# schema.net
KiCad netlist of a schematic drawn in EAGLE
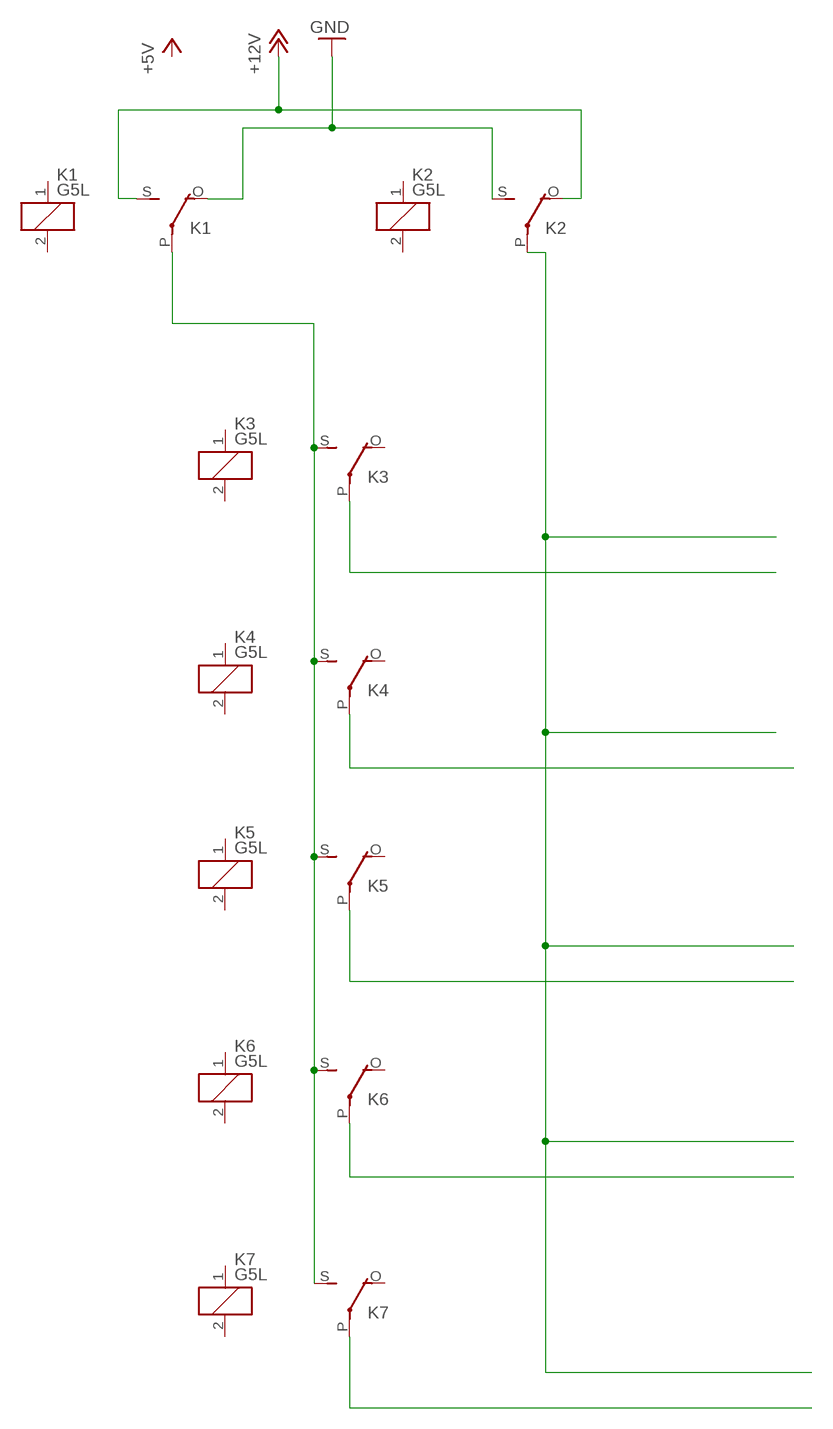
[diagram p0: schematic, sheet 1]

(export (version "E")
  (design (tool "Eeschema 10.0.6"))
  (components
    (comp (ref "K1")
      (value "G5L")
      (footprint "eagle-import:G5LE")
      (libsource (lib "eagle-import") (part "G5L"))
    )
    (comp (ref "K2")
      (value "G5L")
      (footprint "eagle-import:G5LE")
      (libsource (lib "eagle-import") (part "G5L"))
    )
    (comp (ref "K3")
      (value "G5L")
      (footprint "eagle-import:G5LE")
      (libsource (lib "eagle-import") (part "G5L"))
    )
    (comp (ref "K4")
      (value "G5L")
      (footprint "eagle-import:G5LE")
      (libsource (lib "eagle-import") (part "G5L"))
    )
    (comp (ref "K5")
      (value "G5L")
      (footprint "eagle-import:G5LE")
      (libsource (lib "eagle-import") (part "G5L"))
    )
    (comp (ref "K6")
      (value "G5L")
      (footprint "eagle-import:G5LE")
      (libsource (lib "eagle-import") (part "G5L"))
    )
    (comp (ref "K7")
      (value "G5L")
      (footprint "eagle-import:G5LE")
      (libsource (lib "eagle-import") (part "G5L"))
    )
  )
  (nets
    (net (code "2") (name "+12V") (class "Default")
      (node (ref "K1") (pin "S") (pinfunction "S_S") (pintype "passive"))
      (node (ref "K2") (pin "O") (pinfunction "O_O") (pintype "passive"))
    )
    (net (code "3") (name "GND") (class "Default")
      (node (ref "K1") (pin "O") (pinfunction "O_O") (pintype "passive"))
      (node (ref "K2") (pin "S") (pinfunction "S_S") (pintype "passive"))
    )
    (net (code "4") (name "Net-(K1-PadP)") (class "Default")
      (node (ref "K1") (pin "P") (pinfunction "P_P") (pintype "passive"))
      (node (ref "K3") (pin "S") (pinfunction "S_S") (pintype "passive"))
      (node (ref "K4") (pin "S") (pinfunction "S_S") (pintype "passive"))
      (node (ref "K5") (pin "S") (pinfunction "S_S") (pintype "passive"))
      (node (ref "K6") (pin "S") (pinfunction "S_S") (pintype "passive"))
      (node (ref "K7") (pin "S") (pinfunction "S_S") (pintype "passive"))
    )
    (net (code "5") (name "unconnected-(K1-Pad1)") (class "Default")
      (node (ref "K1") (pin "1") (pinfunction "1_1") (pintype "passive"))
    )
    (net (code "6") (name "unconnected-(K1-Pad2)") (class "Default")
      (node (ref "K1") (pin "2") (pinfunction "2_2") (pintype "passive"))
    )
    (net (code "7") (name "unconnected-(K2-Pad1)") (class "Default")
      (node (ref "K2") (pin "1") (pinfunction "1_1") (pintype "passive"))
    )
    (net (code "8") (name "unconnected-(K2-Pad2)") (class "Default")
      (node (ref "K2") (pin "2") (pinfunction "2_2") (pintype "passive"))
    )
    (net (code "9") (name "unconnected-(K2-PadP)") (class "Default")
      (node (ref "K2") (pin "P") (pinfunction "P_P") (pintype "passive"))
    )
    (net (code "10") (name "unconnected-(K3-Pad1)") (class "Default")
      (node (ref "K3") (pin "1") (pinfunction "1_1") (pintype "passive"))
    )
    (net (code "11") (name "unconnected-(K3-Pad2)") (class "Default")
      (node (ref "K3") (pin "2") (pinfunction "2_2") (pintype "passive"))
    )
    (net (code "12") (name "unconnected-(K3-PadO)") (class "Default")
      (node (ref "K3") (pin "O") (pinfunction "O_O") (pintype "passive"))
    )
    (net (code "13") (name "unconnected-(K3-PadP)") (class "Default")
      (node (ref "K3") (pin "P") (pinfunction "P_P") (pintype "passive"))
    )
    (net (code "14") (name "unconnected-(K4-Pad1)") (class "Default")
      (node (ref "K4") (pin "1") (pinfunction "1_1") (pintype "passive"))
    )
    (net (code "15") (name "unconnected-(K4-Pad2)") (class "Default")
      (node (ref "K4") (pin "2") (pinfunction "2_2") (pintype "passive"))
    )
    (net (code "16") (name "unconnected-(K4-PadO)") (class "Default")
      (node (ref "K4") (pin "O") (pinfunction "O_O") (pintype "passive"))
    )
    (net (code "17") (name "unconnected-(K4-PadP)") (class "Default")
      (node (ref "K4") (pin "P") (pinfunction "P_P") (pintype "passive"))
    )
    (net (code "18") (name "unconnected-(K5-Pad1)") (class "Default")
      (node (ref "K5") (pin "1") (pinfunction "1_1") (pintype "passive"))
    )
    (net (code "19") (name "unconnected-(K5-Pad2)") (class "Default")
      (node (ref "K5") (pin "2") (pinfunction "2_2") (pintype "passive"))
    )
    (net (code "20") (name "unconnected-(K5-PadO)") (class "Default")
      (node (ref "K5") (pin "O") (pinfunction "O_O") (pintype "passive"))
    )
    (net (code "21") (name "unconnected-(K5-PadP)") (class "Default")
      (node (ref "K5") (pin "P") (pinfunction "P_P") (pintype "passive"))
    )
    (net (code "22") (name "unconnected-(K6-Pad1)") (class "Default")
      (node (ref "K6") (pin "1") (pinfunction "1_1") (pintype "passive"))
    )
    (net (code "23") (name "unconnected-(K6-Pad2)") (class "Default")
      (node (ref "K6") (pin "2") (pinfunction "2_2") (pintype "passive"))
    )
    (net (code "24") (name "unconnected-(K6-PadO)") (class "Default")
      (node (ref "K6") (pin "O") (pinfunction "O_O") (pintype "passive"))
    )
    (net (code "25") (name "unconnected-(K6-PadP)") (class "Default")
      (node (ref "K6") (pin "P") (pinfunction "P_P") (pintype "passive"))
    )
    (net (code "26") (name "unconnected-(K7-Pad1)") (class "Default")
      (node (ref "K7") (pin "1") (pinfunction "1_1") (pintype "passive"))
    )
    (net (code "27") (name "unconnected-(K7-Pad2)") (class "Default")
      (node (ref "K7") (pin "2") (pinfunction "2_2") (pintype "passive"))
    )
    (net (code "28") (name "unconnected-(K7-PadO)") (class "Default")
      (node (ref "K7") (pin "O") (pinfunction "O_O") (pintype "passive"))
    )
    (net (code "29") (name "unconnected-(K7-PadP)") (class "Default")
      (node (ref "K7") (pin "P") (pinfunction "P_P") (pintype "passive"))
    )
  )
)
